# Sheet1.net
KiCad netlist of a schematic drawn in Altium Designer
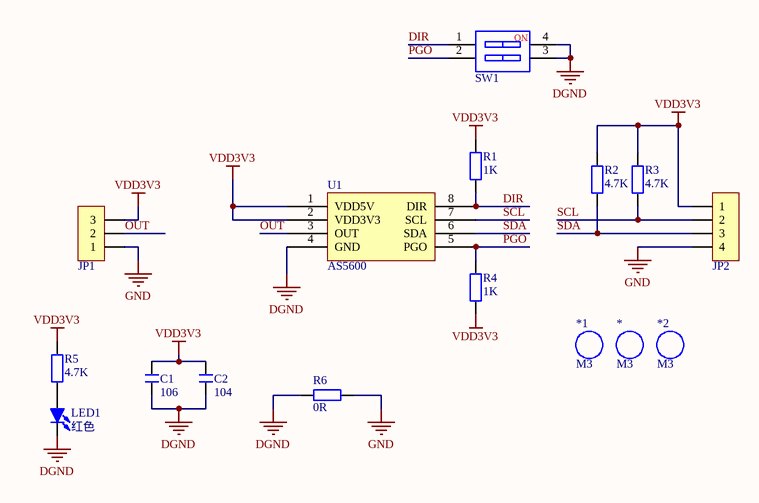
[diagram p0: Sheet1.SchDoc]

(export (version "E")
  (design (tool "Eeschema 10.0.6"))
  (components
    (comp (ref "*")
      (value "M3")
      (footprint "M3 125X200")
      (description "铜柱孔")
      (fields (field (name "版权归属") "源创客"))
      (libsource (lib "15.1 - 未分类器件") (part "M3"))
    )
    (comp (ref "*1")
      (value "M3")
      (footprint "M3 125X200")
      (description "铜柱孔")
      (fields (field (name "版权归属") "源创客"))
      (libsource (lib "15.1 - 未分类器件") (part "M3"))
    )
    (comp (ref "*2")
      (value "M3")
      (footprint "M3 125X200")
      (description "铜柱孔")
      (fields (field (name "版权归属") "源创客"))
      (libsource (lib "15.1 - 未分类器件") (part "M3"))
    )
    (comp (ref "C1")
      (value "106")
      (footprint "C 0603_M")
      (description "无极性贴片电容")
      (fields (field (name "版权归属") "源创客"))
      (libsource (lib "3.1   - 电阻-电容-电感") (part "C"))
    )
    (comp (ref "C2")
      (value "104")
      (footprint "C 0603_M")
      (description "无极性贴片电容")
      (fields (field (name "版权归属") "源创客"))
      (libsource (lib "3.1   - 电阻-电容-电感") (part "C"))
    )
    (comp (ref "JP1")
      (value "HDR-1X3")
      (footprint "MX 1.25-WS-3P")
      (description "3P接插件")
      (fields (field (name "版权归属") "源创客"))
      (libsource (lib "4.2   - 接插件-脚距1.25") (part "Header 3"))
    )
    (comp (ref "JP2")
      (value "HDR-1X4")
      (footprint "MX 1.25-WS-4P")
      (description "4P接插件")
      (fields (field (name "版权归属") "源创客"))
      (libsource (lib "4.2   - 接插件-脚距1.25") (part "Header 4"))
    )
    (comp (ref "LED1")
      (value "红色")
      (footprint "LED 0603G")
      (description "贴片LED")
      (fields (field (name "版权归属") "源创客"))
      (libsource (lib "9.1   - LED") (part "LED-SMD"))
    )
    (comp (ref "R1")
      (value "1K")
      (footprint "R 0805_L")
      (description "贴片电阻")
      (fields (field (name "版权归属") "源创客"))
      (libsource (lib "3.1   - 电阻-电容-电感") (part "R"))
    )
    (comp (ref "R2")
      (value "4.7K")
      (footprint "R 0805_L")
      (description "贴片电阻")
      (fields (field (name "版权归属") "源创客"))
      (libsource (lib "3.1   - 电阻-电容-电感") (part "R"))
    )
    (comp (ref "R3")
      (value "4.7K")
      (footprint "R 0805_L")
      (description "贴片电阻")
      (fields (field (name "版权归属") "源创客"))
      (libsource (lib "3.1   - 电阻-电容-电感") (part "R"))
    )
    (comp (ref "R4")
      (value "1K")
      (footprint "R 0805_L")
      (description "贴片电阻")
      (fields (field (name "版权归属") "源创客"))
      (libsource (lib "3.1   - 电阻-电容-电感") (part "R"))
    )
    (comp (ref "R5")
      (value "4.7K")
      (footprint "R 0805_L")
      (description "贴片电阻")
      (fields (field (name "版权归属") "源创客"))
      (libsource (lib "3.1   - 电阻-电容-电感") (part "R"))
    )
    (comp (ref "R6")
      (value "0R")
      (footprint "R 0603_L")
      (description "贴片电阻")
      (fields (field (name "版权归属") "源创客"))
      (libsource (lib "3.1   - 电阻-电容-电感") (part "R"))
    )
    (comp (ref "SW1")
      (value "CSW-2P")
      (footprint "CSW1.27 SMD-2P")
      (description "2路编码开关")
      (fields (field (name "版权归属") "源创客"))
      (libsource (lib "5.1   - 按键-开关") (part "CSW-2P"))
    )
    (comp (ref "U1") (value "AS5600") (footprint "SOIC_8") (libsource (lib "Schlib1") (part "AS5600")))
  )
  (nets
    (net (code "1") (name "/DIR") (class "Default")
      (node (ref "R1") (pin "1") (pinfunction "1_1") (pintype "passive"))
      (node (ref "SW1") (pin "1") (pinfunction "1_1") (pintype "passive"))
      (node (ref "U1") (pin "8") (pinfunction "DIR_8") (pintype "passive"))
    )
    (net (code "2") (name "/OUT") (class "Default")
      (node (ref "JP1") (pin "2") (pinfunction "2_2") (pintype "passive"))
      (node (ref "U1") (pin "3") (pinfunction "OUT_3") (pintype "passive"))
    )
    (net (code "3") (name "/PGO") (class "Default")
      (node (ref "R4") (pin "2") (pinfunction "2_2") (pintype "passive"))
      (node (ref "SW1") (pin "2") (pinfunction "2_2") (pintype "passive"))
      (node (ref "U1") (pin "5") (pinfunction "PGO_5") (pintype "passive"))
    )
    (net (code "4") (name "/SCL") (class "Default")
      (node (ref "JP2") (pin "2") (pinfunction "2_2") (pintype "passive"))
      (node (ref "R3") (pin "1") (pinfunction "1_1") (pintype "passive"))
      (node (ref "U1") (pin "7") (pinfunction "SCL_7") (pintype "passive"))
    )
    (net (code "5") (name "/SDA") (class "Default")
      (node (ref "JP2") (pin "3") (pinfunction "3_3") (pintype "passive"))
      (node (ref "R2") (pin "1") (pinfunction "1_1") (pintype "passive"))
      (node (ref "U1") (pin "6") (pinfunction "SDA_6") (pintype "passive"))
    )
    (net (code "6") (name "DGND") (class "Default")
      (node (ref "C1") (pin "1") (pinfunction "1_1") (pintype "passive"))
      (node (ref "C2") (pin "1") (pinfunction "1_1") (pintype "passive"))
      (node (ref "LED1") (pin "2") (pinfunction "K_2") (pintype "passive"))
      (node (ref "R6") (pin "1") (pinfunction "1_1") (pintype "passive"))
      (node (ref "SW1") (pin "3") (pinfunction "3_3") (pintype "passive"))
      (node (ref "SW1") (pin "4") (pinfunction "4_4") (pintype "passive"))
      (node (ref "U1") (pin "4") (pinfunction "GND_4") (pintype "passive"))
    )
    (net (code "7") (name "GND") (class "Default")
      (node (ref "JP1") (pin "1") (pinfunction "1_1") (pintype "passive"))
      (node (ref "JP2") (pin "4") (pinfunction "4_4") (pintype "passive"))
      (node (ref "R6") (pin "2") (pinfunction "2_2") (pintype "passive"))
    )
    (net (code "8") (name "Net-(LED1-A)") (class "Default")
      (node (ref "LED1") (pin "1") (pinfunction "A_1") (pintype "passive"))
      (node (ref "R5") (pin "1") (pinfunction "1_1") (pintype "passive"))
    )
    (net (code "9") (name "VDD3V3") (class "Default")
      (node (ref "C1") (pin "2") (pinfunction "2_2") (pintype "passive"))
      (node (ref "C2") (pin "2") (pinfunction "2_2") (pintype "passive"))
      (node (ref "JP1") (pin "3") (pinfunction "3_3") (pintype "passive"))
      (node (ref "JP2") (pin "1") (pinfunction "1_1") (pintype "passive"))
      (node (ref "R1") (pin "2") (pinfunction "2_2") (pintype "passive"))
      (node (ref "R2") (pin "2") (pinfunction "2_2") (pintype "passive"))
      (node (ref "R3") (pin "2") (pinfunction "2_2") (pintype "passive"))
      (node (ref "R4") (pin "1") (pinfunction "1_1") (pintype "passive"))
      (node (ref "R5") (pin "2") (pinfunction "2_2") (pintype "passive"))
      (node (ref "U1") (pin "1") (pinfunction "VDD5V_1") (pintype "passive"))
      (node (ref "U1") (pin "2") (pinfunction "VDD3V3_2") (pintype "passive"))
    )
  )
)
